# openbridge.net
KiCad netlist of a schematic drawn in EAGLE
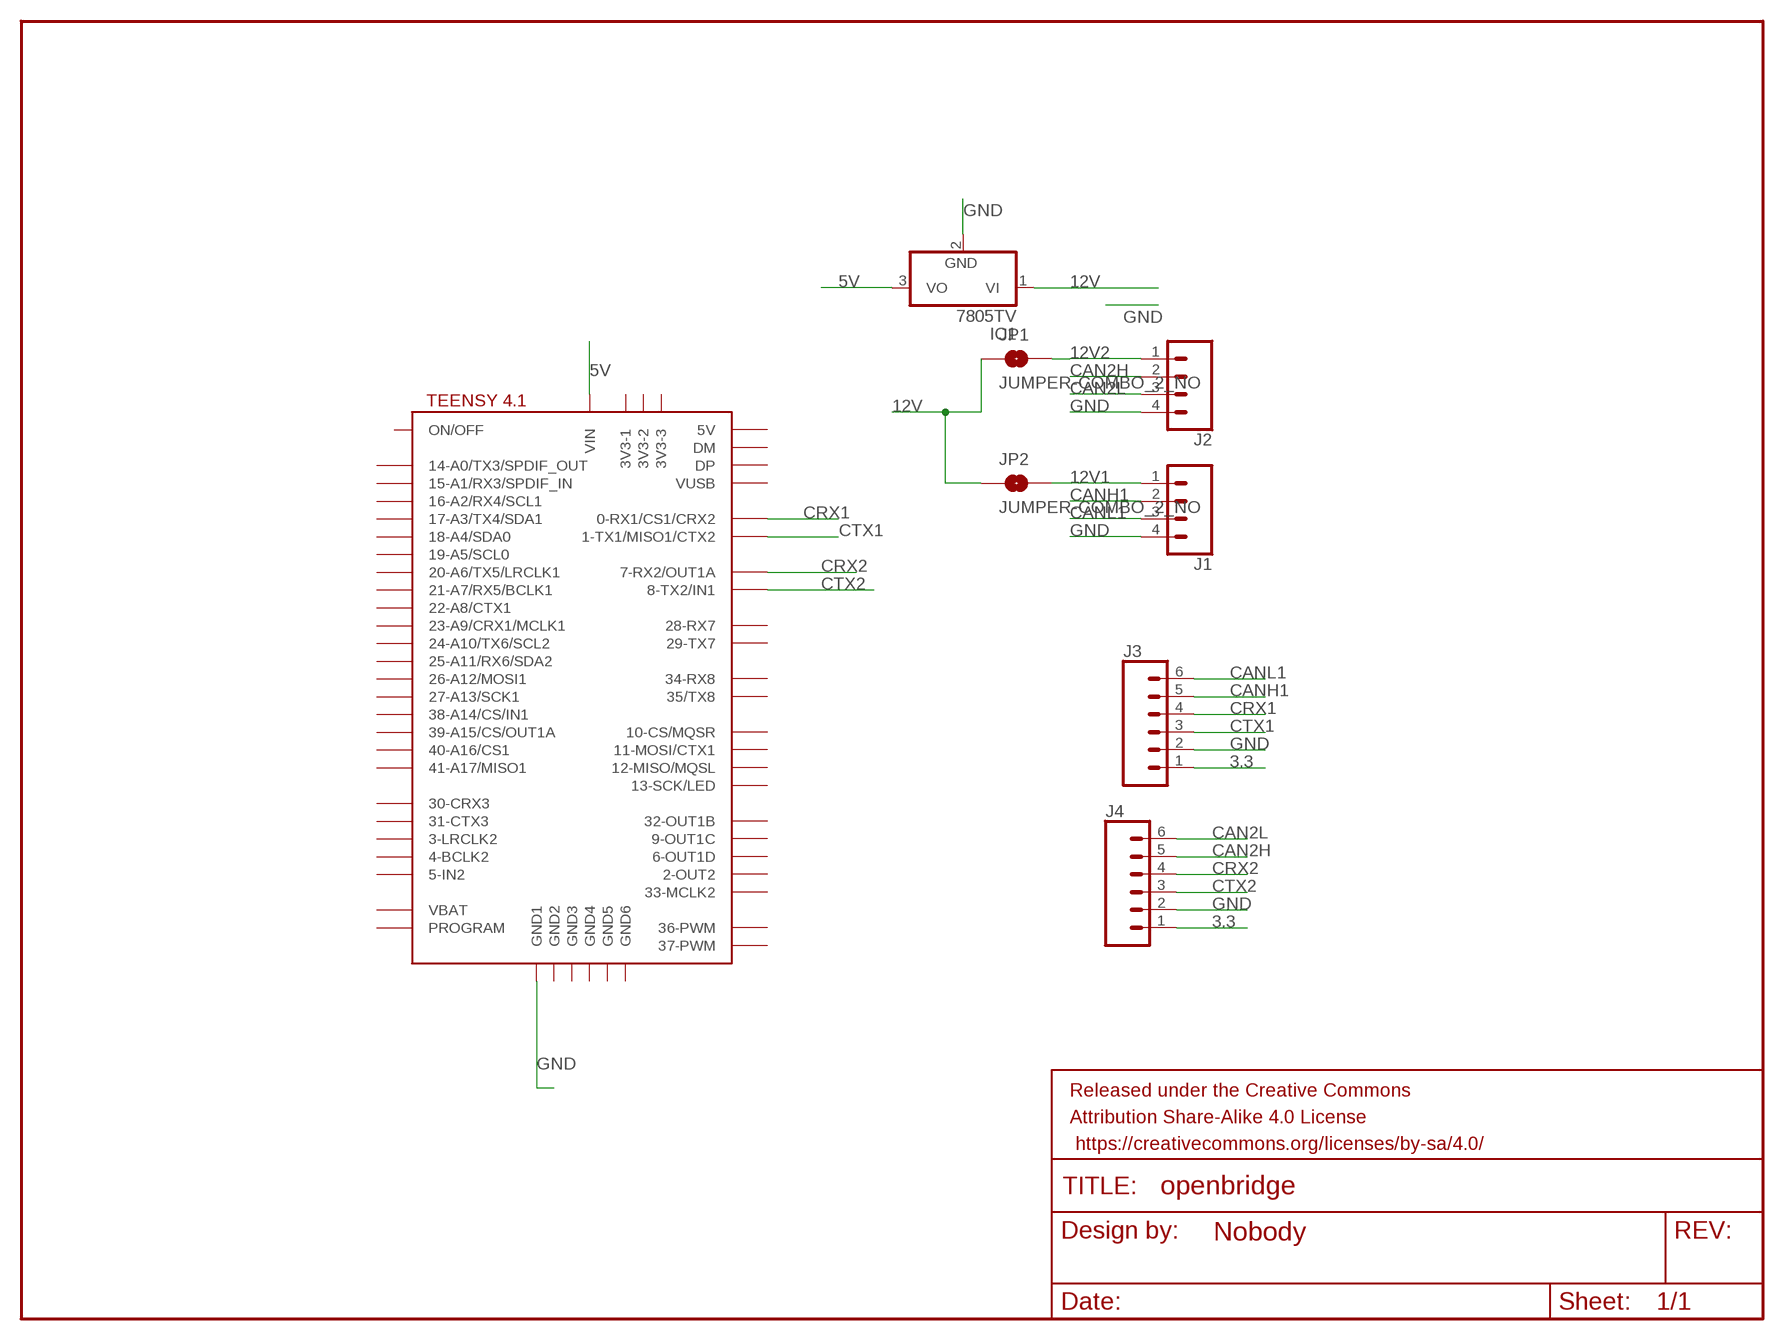
[diagram p0: schematic, sheet 1]

(export (version "E")
  (design (tool "Eeschema 10.0.6"))
  (components
    (comp (ref "FRAME1")
      (value "FRAME-LETTERNO_PACKAGE")
      (footprint "eagle-import:DUMMY")
      (fields (field (name "DESIGNER") "Nobody"))
      (libsource (lib "eagle-import") (part "FRAME-LETTERNO_PACKAGE"))
    )
    (comp (ref "IC1")
      (value "7805TV")
      (footprint "eagle-import:TO220V")
      (libsource (lib "eagle-import") (part "78TV05"))
    )
    (comp (ref "J1")
      (value "CONN_04SCREW")
      (footprint "eagle-import:SCREWTERMINAL-3.5MM-4")
      (libsource (lib "eagle-import") (part "CONN_04SCREW"))
    )
    (comp (ref "J2")
      (value "CONN_04SCREW")
      (footprint "eagle-import:SCREWTERMINAL-3.5MM-4")
      (libsource (lib "eagle-import") (part "CONN_04SCREW"))
    )
    (comp (ref "J3")
      (value "CONN_06LONGPADS")
      (footprint "eagle-import:1X06_LONGPADS")
      (libsource (lib "eagle-import") (part "CONN_06LONGPADS"))
    )
    (comp (ref "J4")
      (value "CONN_06LONGPADS")
      (footprint "eagle-import:1X06_LONGPADS")
      (libsource (lib "eagle-import") (part "CONN_06LONGPADS"))
    )
    (comp (ref "JP1")
      (value "JUMPER-COMBO_2_NO")
      (footprint "eagle-import:COMBO-JUMPER_2_NO")
      (libsource (lib "eagle-import") (part "JUMPER-COMBO_2_NO"))
    )
    (comp (ref "JP2")
      (value "JUMPER-COMBO_2_NO")
      (footprint "eagle-import:COMBO-JUMPER_2_NO")
      (libsource (lib "eagle-import") (part "JUMPER-COMBO_2_NO"))
    )
    (comp (ref "U$1")
      (value "TEENSY41-E")
      (footprint "eagle-import:TENNSY41-E")
      (libsource (lib "eagle-import") (part "TEENSY41-E"))
    )
  )
  (nets
    (net (code "1") (name "/3.3") (class "Default")
      (node (ref "J3") (pin "1") (pinfunction "1_1") (pintype "passive"))
      (node (ref "J4") (pin "1") (pinfunction "1_1") (pintype "passive"))
    )
    (net (code "2") (name "/5V") (class "Default")
      (node (ref "IC1") (pin "3") (pinfunction "VO_3") (pintype "passive"))
      (node (ref "U$1") (pin "VIN") (pinfunction "VIN_VIN") (pintype "bidirectional"))
    )
    (net (code "3") (name "/12V") (class "Default")
      (node (ref "IC1") (pin "1") (pinfunction "VI_1") (pintype "input"))
      (node (ref "JP1") (pin "1") (pinfunction "1_1") (pintype "passive"))
      (node (ref "JP1") (pin "3") (pinfunction "1_3") (pintype "passive"))
      (node (ref "JP2") (pin "1") (pinfunction "1_1") (pintype "passive"))
      (node (ref "JP2") (pin "3") (pinfunction "1_3") (pintype "passive"))
    )
    (net (code "4") (name "/12V1") (class "Default")
      (node (ref "J1") (pin "1") (pinfunction "1_1") (pintype "passive"))
      (node (ref "JP2") (pin "2") (pinfunction "2_2") (pintype "passive"))
      (node (ref "JP2") (pin "4") (pinfunction "2_4") (pintype "passive"))
    )
    (net (code "5") (name "/12V2") (class "Default")
      (node (ref "J2") (pin "1") (pinfunction "1_1") (pintype "passive"))
      (node (ref "JP1") (pin "2") (pinfunction "2_2") (pintype "passive"))
      (node (ref "JP1") (pin "4") (pinfunction "2_4") (pintype "passive"))
    )
    (net (code "6") (name "/CAN2H") (class "Default")
      (node (ref "J2") (pin "2") (pinfunction "2_2") (pintype "passive"))
      (node (ref "J4") (pin "5") (pinfunction "5_5") (pintype "passive"))
    )
    (net (code "7") (name "/CAN2L") (class "Default")
      (node (ref "J2") (pin "3") (pinfunction "3_3") (pintype "passive"))
      (node (ref "J4") (pin "6") (pinfunction "6_6") (pintype "passive"))
    )
    (net (code "8") (name "/CANH1") (class "Default")
      (node (ref "J1") (pin "2") (pinfunction "2_2") (pintype "passive"))
      (node (ref "J3") (pin "5") (pinfunction "5_5") (pintype "passive"))
    )
    (net (code "9") (name "/CANL1") (class "Default")
      (node (ref "J1") (pin "3") (pinfunction "3_3") (pintype "passive"))
      (node (ref "J3") (pin "6") (pinfunction "6_6") (pintype "passive"))
    )
    (net (code "10") (name "/CRX1") (class "Default")
      (node (ref "J3") (pin "4") (pinfunction "4_4") (pintype "passive"))
      (node (ref "U$1") (pin "0-RX1/CS1/CRX2") (pinfunction "0-RX1/CS1/CRX2_0-RX1/CS1/CRX2") (pintype "bidirectional"))
    )
    (net (code "11") (name "/CRX2") (class "Default")
      (node (ref "J4") (pin "4") (pinfunction "4_4") (pintype "passive"))
      (node (ref "U$1") (pin "7-RX2/OUT1A") (pinfunction "7-RX2/OUT1A_7-RX2/OUT1A") (pintype "bidirectional"))
    )
    (net (code "12") (name "/CTX1") (class "Default")
      (node (ref "J3") (pin "3") (pinfunction "3_3") (pintype "passive"))
      (node (ref "U$1") (pin "1-TX1/MISO1/CTX2") (pinfunction "1-TX1/MISO1/CTX2_1-TX1/MISO1/CTX2") (pintype "bidirectional"))
    )
    (net (code "13") (name "/CTX2") (class "Default")
      (node (ref "J4") (pin "3") (pinfunction "3_3") (pintype "passive"))
      (node (ref "U$1") (pin "8-TX2/IN1") (pinfunction "8-TX2/IN1_8-TX2/IN1") (pintype "bidirectional"))
    )
    (net (code "14") (name "/GND") (class "Default")
      (node (ref "IC1") (pin "2") (pinfunction "GND_2") (pintype "passive"))
      (node (ref "J1") (pin "4") (pinfunction "4_4") (pintype "passive"))
      (node (ref "J2") (pin "4") (pinfunction "4_4") (pintype "passive"))
      (node (ref "J3") (pin "2") (pinfunction "2_2") (pintype "passive"))
      (node (ref "J4") (pin "2") (pinfunction "2_2") (pintype "passive"))
      (node (ref "U$1") (pin "GND1") (pinfunction "GND1_GND1") (pintype "bidirectional"))
    )
    (net (code "15") (name "unconnected-(U$1-5V-Pad+5V)") (class "Default")
      (node (ref "U$1") (pin "+5V") (pinfunction "5V_+5V") (pintype "bidirectional"))
    )
    (net (code "16") (name "unconnected-(U$1-10-CS{slash}MQSR-Pad10-CS\\MQSR)") (class "Default")
      (node (ref "U$1") (pin "10-CS\\MQSR") (pinfunction "10-CS/MQSR_10-CS\\MQSR") (pintype "bidirectional"))
    )
    (net (code "17") (name "unconnected-(U$1-35{slash}TX8-Pad35-TX8)") (class "Default")
      (node (ref "U$1") (pin "35-TX8") (pinfunction "35/TX8_35-TX8") (pintype "bidirectional"))
    )
    (net (code "18") (name "unconnected-(U$1-Pad2-OUT2)") (class "Default")
      (node (ref "U$1") (pin "2-OUT2") (pinfunction "2-OUT2_2-OUT2") (pintype "bidirectional"))
    )
    (net (code "19") (name "unconnected-(U$1-Pad3-LRCLK2)") (class "Default")
      (node (ref "U$1") (pin "3-LRCLK2") (pinfunction "3-LRCLK2_3-LRCLK2") (pintype "bidirectional"))
    )
    (net (code "20") (name "unconnected-(U$1-Pad3V3-1)") (class "Default")
      (node (ref "U$1") (pin "3V3-1") (pinfunction "3V3-1_3V3-1") (pintype "bidirectional"))
    )
    (net (code "21") (name "unconnected-(U$1-Pad3V3-2)") (class "Default")
      (node (ref "U$1") (pin "3V3-2") (pinfunction "3V3-2_3V3-2") (pintype "bidirectional"))
    )
    (net (code "22") (name "unconnected-(U$1-Pad3V3-3)") (class "Default")
      (node (ref "U$1") (pin "3V3-3") (pinfunction "3V3-3_3V3-3") (pintype "bidirectional"))
    )
    (net (code "23") (name "unconnected-(U$1-Pad4-BCLK2)") (class "Default")
      (node (ref "U$1") (pin "4-BCLK2") (pinfunction "4-BCLK2_4-BCLK2") (pintype "bidirectional"))
    )
    (net (code "24") (name "unconnected-(U$1-Pad5-IN2)") (class "Default")
      (node (ref "U$1") (pin "5-IN2") (pinfunction "5-IN2_5-IN2") (pintype "bidirectional"))
    )
    (net (code "25") (name "unconnected-(U$1-Pad6-OUT1D)") (class "Default")
      (node (ref "U$1") (pin "6-OUT1D") (pinfunction "6-OUT1D_6-OUT1D") (pintype "bidirectional"))
    )
    (net (code "26") (name "unconnected-(U$1-Pad9-OUT1C)") (class "Default")
      (node (ref "U$1") (pin "9-OUT1C") (pinfunction "9-OUT1C_9-OUT1C") (pintype "bidirectional"))
    )
    (net (code "27") (name "unconnected-(U$1-Pad11-MOSI{slash}CTX1)") (class "Default")
      (node (ref "U$1") (pin "11-MOSI/CTX1") (pinfunction "11-MOSI/CTX1_11-MOSI/CTX1") (pintype "bidirectional"))
    )
    (net (code "28") (name "unconnected-(U$1-Pad12-MISO{slash}MQSL)") (class "Default")
      (node (ref "U$1") (pin "12-MISO/MQSL") (pinfunction "12-MISO/MQSL_12-MISO/MQSL") (pintype "bidirectional"))
    )
    (net (code "29") (name "unconnected-(U$1-Pad13-SCK{slash}LED)") (class "Default")
      (node (ref "U$1") (pin "13-SCK/LED") (pinfunction "13-SCK/LED_13-SCK/LED") (pintype "bidirectional"))
    )
    (net (code "30") (name "unconnected-(U$1-Pad14-A0{slash}TX3{slash}SPDIF_OUT)") (class "Default")
      (node (ref "U$1") (pin "14-A0/TX3/SPDIF_OUT") (pinfunction "14-A0/TX3/SPDIF_OUT_14-A0/TX3/SPDIF_OUT") (pintype "bidirectional"))
    )
    (net (code "31") (name "unconnected-(U$1-Pad15-A1{slash}RX3{slash}SPDIF_IN)") (class "Default")
      (node (ref "U$1") (pin "15-A1/RX3/SPDIF_IN") (pinfunction "15-A1/RX3/SPDIF_IN_15-A1/RX3/SPDIF_IN") (pintype "bidirectional"))
    )
    (net (code "32") (name "unconnected-(U$1-Pad16-A2{slash}RX4{slash}SCL1)") (class "Default")
      (node (ref "U$1") (pin "16-A2/RX4/SCL1") (pinfunction "16-A2/RX4/SCL1_16-A2/RX4/SCL1") (pintype "bidirectional"))
    )
    (net (code "33") (name "unconnected-(U$1-Pad17-A3{slash}TX4{slash}SDA1)") (class "Default")
      (node (ref "U$1") (pin "17-A3/TX4/SDA1") (pinfunction "17-A3/TX4/SDA1_17-A3/TX4/SDA1") (pintype "bidirectional"))
    )
    (net (code "34") (name "unconnected-(U$1-Pad18-A4{slash}SDA0)") (class "Default")
      (node (ref "U$1") (pin "18-A4/SDA0") (pinfunction "18-A4/SDA0_18-A4/SDA0") (pintype "bidirectional"))
    )
    (net (code "35") (name "unconnected-(U$1-Pad19-A5{slash}SCL0)") (class "Default")
      (node (ref "U$1") (pin "19-A5/SCL0") (pinfunction "19-A5/SCL0_19-A5/SCL0") (pintype "bidirectional"))
    )
    (net (code "36") (name "unconnected-(U$1-Pad20-A6{slash}TX5{slash}LRCLK1)") (class "Default")
      (node (ref "U$1") (pin "20-A6/TX5/LRCLK1") (pinfunction "20-A6/TX5/LRCLK1_20-A6/TX5/LRCLK1") (pintype "bidirectional"))
    )
    (net (code "37") (name "unconnected-(U$1-Pad21-A7{slash}RX5{slash}BCLK1)") (class "Default")
      (node (ref "U$1") (pin "21-A7/RX5/BCLK1") (pinfunction "21-A7/RX5/BCLK1_21-A7/RX5/BCLK1") (pintype "bidirectional"))
    )
    (net (code "38") (name "unconnected-(U$1-Pad22-A8{slash}CTX1)") (class "Default")
      (node (ref "U$1") (pin "22-A8/CTX1") (pinfunction "22-A8/CTX1_22-A8/CTX1") (pintype "bidirectional"))
    )
    (net (code "39") (name "unconnected-(U$1-Pad23-A9{slash}CRX1{slash}MCLK1)") (class "Default")
      (node (ref "U$1") (pin "23-A9/CRX1/MCLK1") (pinfunction "23-A9/CRX1/MCLK1_23-A9/CRX1/MCLK1") (pintype "bidirectional"))
    )
    (net (code "40") (name "unconnected-(U$1-Pad24-A10{slash}TX6{slash}SCL2)") (class "Default")
      (node (ref "U$1") (pin "24-A10/TX6/SCL2") (pinfunction "24-A10/TX6/SCL2_24-A10/TX6/SCL2") (pintype "bidirectional"))
    )
    (net (code "41") (name "unconnected-(U$1-Pad25-A11{slash}RX6{slash}SDA2)") (class "Default")
      (node (ref "U$1") (pin "25-A11/RX6/SDA2") (pinfunction "25-A11/RX6/SDA2_25-A11/RX6/SDA2") (pintype "bidirectional"))
    )
    (net (code "42") (name "unconnected-(U$1-Pad26-A12{slash}MOSI1)") (class "Default")
      (node (ref "U$1") (pin "26-A12/MOSI1") (pinfunction "26-A12/MOSI1_26-A12/MOSI1") (pintype "bidirectional"))
    )
    (net (code "43") (name "unconnected-(U$1-Pad27-A13{slash}SCK1)") (class "Default")
      (node (ref "U$1") (pin "27-A13/SCK1") (pinfunction "27-A13/SCK1_27-A13/SCK1") (pintype "bidirectional"))
    )
    (net (code "44") (name "unconnected-(U$1-Pad28-RX7)") (class "Default")
      (node (ref "U$1") (pin "28-RX7") (pinfunction "28-RX7_28-RX7") (pintype "bidirectional"))
    )
    (net (code "45") (name "unconnected-(U$1-Pad29-TX7)") (class "Default")
      (node (ref "U$1") (pin "29-TX7") (pinfunction "29-TX7_29-TX7") (pintype "bidirectional"))
    )
    (net (code "46") (name "unconnected-(U$1-Pad30-CRX3)") (class "Default")
      (node (ref "U$1") (pin "30-CRX3") (pinfunction "30-CRX3_30-CRX3") (pintype "bidirectional"))
    )
    (net (code "47") (name "unconnected-(U$1-Pad31-CTX3)") (class "Default")
      (node (ref "U$1") (pin "31-CTX3") (pinfunction "31-CTX3_31-CTX3") (pintype "bidirectional"))
    )
    (net (code "48") (name "unconnected-(U$1-Pad32-OUT1B)") (class "Default")
      (node (ref "U$1") (pin "32-OUT1B") (pinfunction "32-OUT1B_32-OUT1B") (pintype "bidirectional"))
    )
    (net (code "49") (name "unconnected-(U$1-Pad33-MCLK2)") (class "Default")
      (node (ref "U$1") (pin "33-MCLK2") (pinfunction "33-MCLK2_33-MCLK2") (pintype "bidirectional"))
    )
    (net (code "50") (name "unconnected-(U$1-Pad34-RX8)") (class "Default")
      (node (ref "U$1") (pin "34-RX8") (pinfunction "34-RX8_34-RX8") (pintype "bidirectional"))
    )
    (net (code "51") (name "unconnected-(U$1-Pad36-PWM)") (class "Default")
      (node (ref "U$1") (pin "36-PWM") (pinfunction "36-PWM_36-PWM") (pintype "bidirectional"))
    )
    (net (code "52") (name "unconnected-(U$1-Pad37-PWM)") (class "Default")
      (node (ref "U$1") (pin "37-PWM") (pinfunction "37-PWM_37-PWM") (pintype "bidirectional"))
    )
    (net (code "53") (name "unconnected-(U$1-Pad38-A14{slash}CS{slash}IN1)") (class "Default")
      (node (ref "U$1") (pin "38-A14/CS/IN1") (pinfunction "38-A14/CS/IN1_38-A14/CS/IN1") (pintype "bidirectional"))
    )
    (net (code "54") (name "unconnected-(U$1-Pad39-A15{slash}CS{slash}OUT1A)") (class "Default")
      (node (ref "U$1") (pin "39-A15/CS/OUT1A") (pinfunction "39-A15/CS/OUT1A_39-A15/CS/OUT1A") (pintype "bidirectional"))
    )
    (net (code "55") (name "unconnected-(U$1-Pad40-A16{slash}CS1)") (class "Default")
      (node (ref "U$1") (pin "40-A16/CS1") (pinfunction "40-A16/CS1_40-A16/CS1") (pintype "bidirectional"))
    )
    (net (code "56") (name "unconnected-(U$1-Pad41-A17{slash}MISO1)") (class "Default")
      (node (ref "U$1") (pin "41-A17/MISO1") (pinfunction "41-A17/MISO1_41-A17/MISO1") (pintype "bidirectional"))
    )
    (net (code "57") (name "unconnected-(U$1-PadDM)") (class "Default")
      (node (ref "U$1") (pin "DM") (pinfunction "DM_DM") (pintype "bidirectional"))
    )
    (net (code "58") (name "unconnected-(U$1-PadDP)") (class "Default")
      (node (ref "U$1") (pin "DP") (pinfunction "DP_DP") (pintype "bidirectional"))
    )
    (net (code "59") (name "unconnected-(U$1-PadGND2)") (class "Default")
      (node (ref "U$1") (pin "GND2") (pinfunction "GND2_GND2") (pintype "bidirectional"))
    )
    (net (code "60") (name "unconnected-(U$1-PadGND3)") (class "Default")
      (node (ref "U$1") (pin "GND3") (pinfunction "GND3_GND3") (pintype "bidirectional"))
    )
    (net (code "61") (name "unconnected-(U$1-PadGND4)") (class "Default")
      (node (ref "U$1") (pin "GND4") (pinfunction "GND4_GND4") (pintype "bidirectional"))
    )
    (net (code "62") (name "unconnected-(U$1-PadGND5)") (class "Default")
      (node (ref "U$1") (pin "GND5") (pinfunction "GND5_GND5") (pintype "bidirectional"))
    )
    (net (code "63") (name "unconnected-(U$1-PadGND6)") (class "Default")
      (node (ref "U$1") (pin "GND6") (pinfunction "GND6_GND6") (pintype "bidirectional"))
    )
    (net (code "64") (name "unconnected-(U$1-PadON{slash}OFF)") (class "Default")
      (node (ref "U$1") (pin "ON/OFF") (pinfunction "ON/OFF_ON/OFF") (pintype "bidirectional"))
    )
    (net (code "65") (name "unconnected-(U$1-PadPROGRAM)") (class "Default")
      (node (ref "U$1") (pin "PROGRAM") (pinfunction "PROGRAM_PROGRAM") (pintype "bidirectional"))
    )
    (net (code "66") (name "unconnected-(U$1-PadVBAT)") (class "Default")
      (node (ref "U$1") (pin "VBAT") (pinfunction "VBAT_VBAT") (pintype "bidirectional"))
    )
    (net (code "67") (name "unconnected-(U$1-PadVUSB)") (class "Default")
      (node (ref "U$1") (pin "VUSB") (pinfunction "VUSB_VUSB") (pintype "bidirectional"))
    )
  )
)
